# FINAL_PROJECT.net
KiCad netlist of a schematic drawn in EAGLE
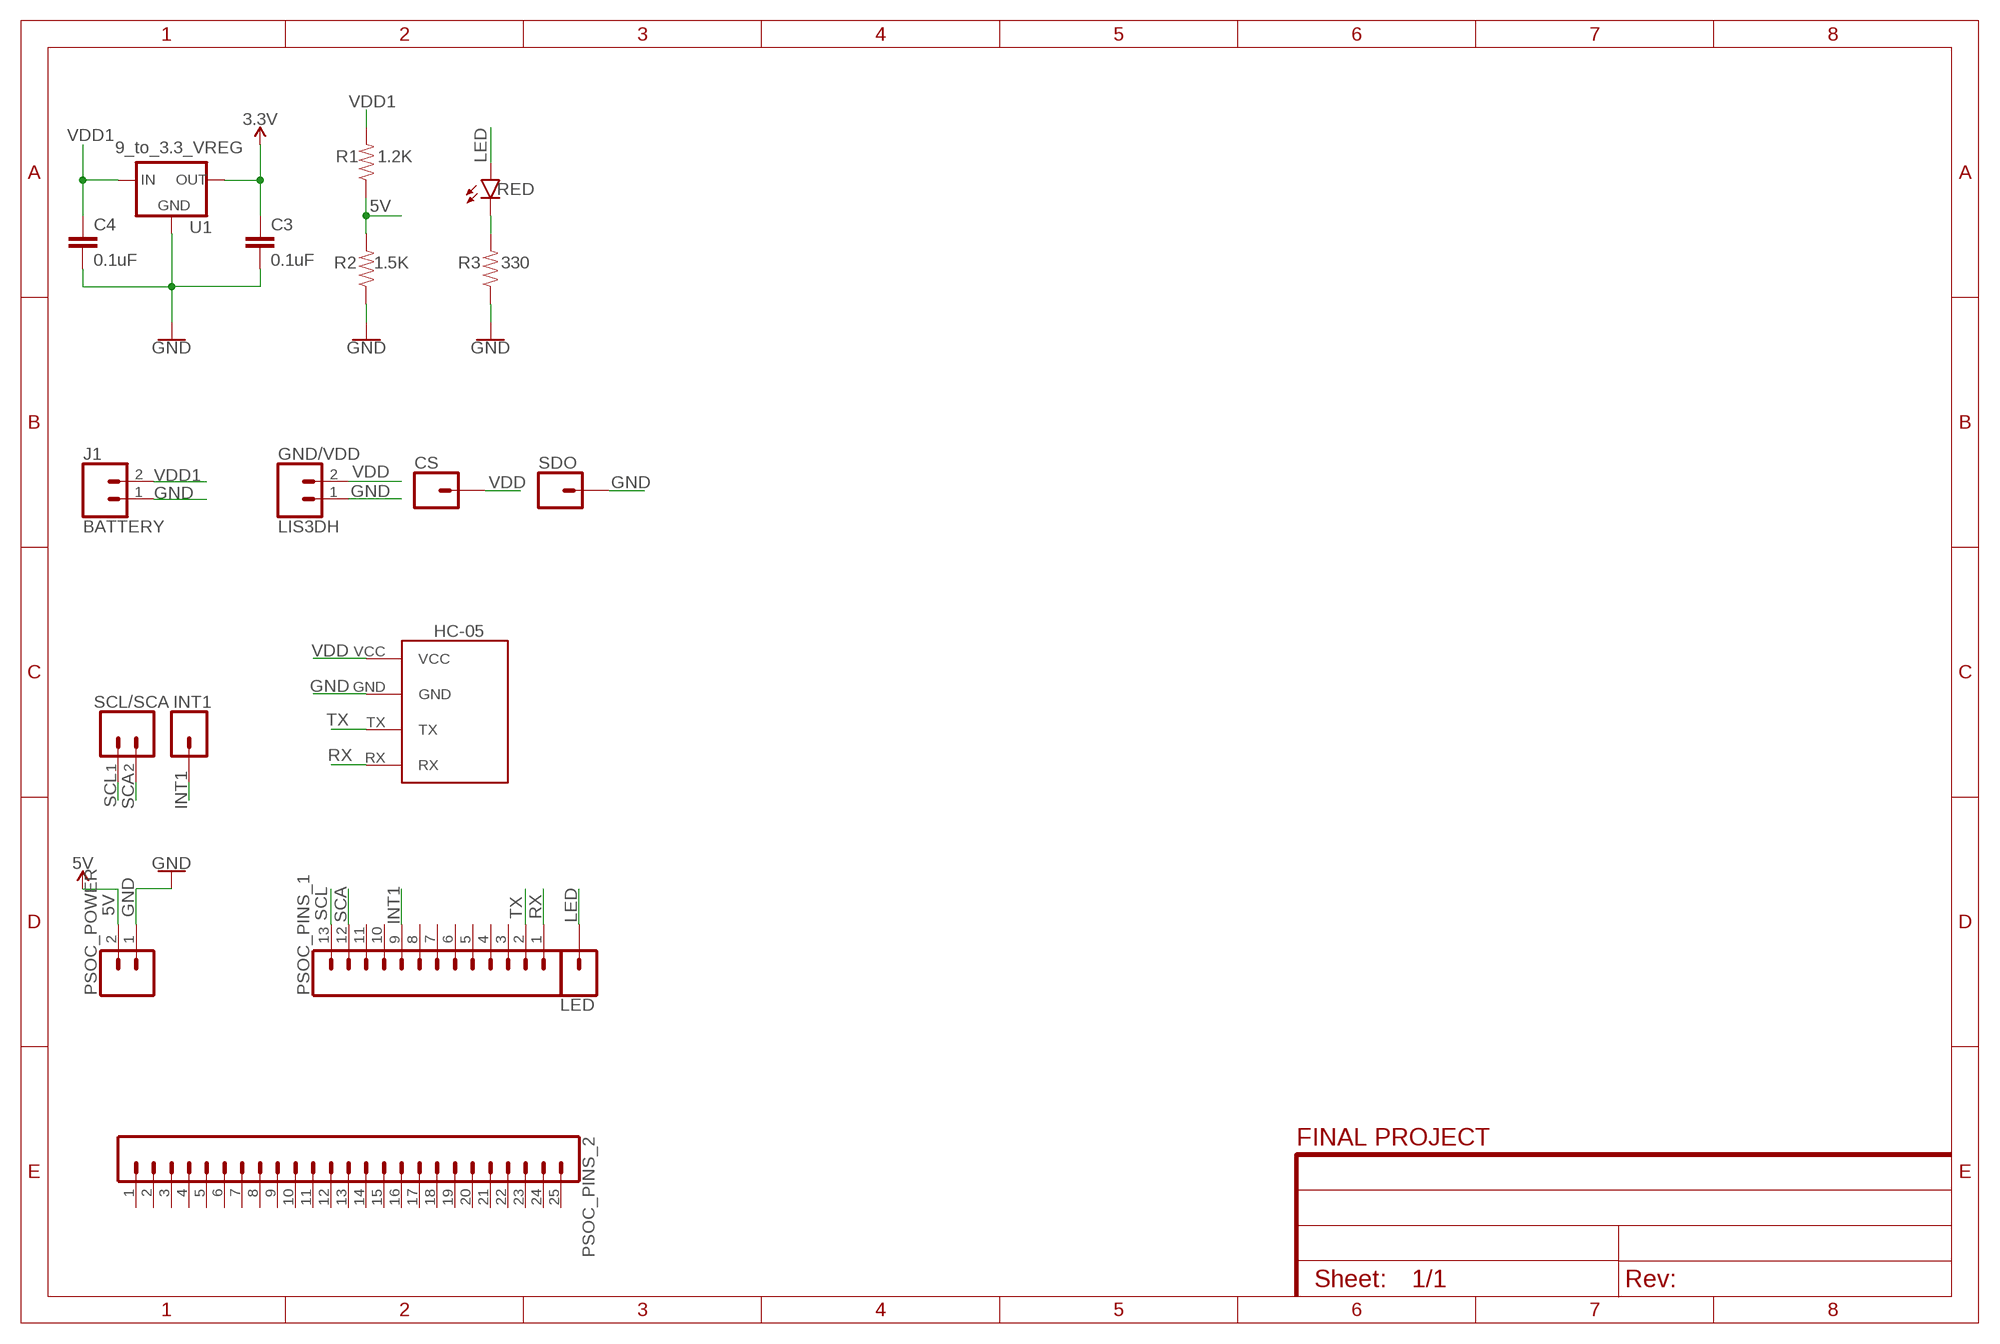
[diagram p0: schematic, sheet 1]

(export (version "E")
  (design (tool "Eeschema 10.0.6"))
  (components
    (comp (ref "C3")
      (value "0.1uF")
      (footprint "eagle-import:CAP-PTH-SMALL-KIT")
      (libsource (lib "eagle-import") (part "0.1UF-KIT-EZ-50V-20%"))
    )
    (comp (ref "C4")
      (value "0.1uF")
      (footprint "eagle-import:CAP-PTH-SMALL-KIT")
      (libsource (lib "eagle-import") (part "0.1UF-KIT-EZ-50V-20%"))
    )
    (comp (ref "CS")
      (value "CONN_01")
      (footprint "eagle-import:1X01")
      (libsource (lib "eagle-import") (part "CONN_01"))
    )
    (comp (ref "GND/VDD")
      (value "LIS3DH")
      (footprint "eagle-import:1X02")
      (libsource (lib "eagle-import") (part "CONN_02"))
    )
    (comp (ref "HC-05")
      (value "BLUETOOTH_BOARD")
      (footprint "eagle-import:BT_BOARD_FOOTPRINT")
      (libsource (lib "eagle-import") (part "BLUETOOTH_BOARD"))
    )
    (comp (ref "INT1")
      (value "CONN_01")
      (footprint "eagle-import:1X01")
      (libsource (lib "eagle-import") (part "CONN_01"))
    )
    (comp (ref "J1")
      (value "BATTERY")
      (footprint "eagle-import:1X02")
      (libsource (lib "eagle-import") (part "CONN_02"))
    )
    (comp (ref "LED")
      (value "CONN_01")
      (footprint "eagle-import:1X01")
      (libsource (lib "eagle-import") (part "CONN_01"))
    )
    (comp (ref "PSOC_PINS_1")
      (value "CONN_13")
      (footprint "eagle-import:1X13")
      (libsource (lib "eagle-import") (part "CONN_13"))
    )
    (comp (ref "PSOC_PINS_2")
      (value "CONN_25")
      (footprint "eagle-import:1X25")
      (libsource (lib "eagle-import") (part "CONN_25"))
    )
    (comp (ref "PSOC_POWER")
      (value "CONN_02")
      (footprint "eagle-import:1X02")
      (libsource (lib "eagle-import") (part "CONN_02"))
    )
    (comp (ref "R1")
      (value "1.2K")
      (footprint "eagle-import:AXIAL-0.3")
      (libsource (lib "eagle-import") (part "330OHM-HORIZ-1/10W-5%"))
    )
    (comp (ref "R2")
      (value "1.5K")
      (footprint "eagle-import:AXIAL-0.3")
      (libsource (lib "eagle-import") (part "330OHM-HORIZ-1/10W-5%"))
    )
    (comp (ref "R3")
      (value "330")
      (footprint "eagle-import:AXIAL-0.3")
      (libsource (lib "eagle-import") (part "330OHM-HORIZ-1/10W-5%"))
    )
    (comp (ref "RED")
      (value "LED3MM")
      (footprint "eagle-import:LED_3MM")
      (libsource (lib "eagle-import") (part "LED3MM"))
    )
    (comp (ref "SCL/SCA")
      (value "CONN_02")
      (footprint "eagle-import:1X02")
      (libsource (lib "eagle-import") (part "CONN_02"))
    )
    (comp (ref "SDO")
      (value "CONN_01")
      (footprint "eagle-import:1X01")
      (libsource (lib "eagle-import") (part "CONN_01"))
    )
    (comp (ref "U1")
      (value "9_to_3.3_VREG")
      (footprint "eagle-import:TO-92")
      (libsource (lib "eagle-import") (part "V_REG_78XXTO-92_UNTESTED"))
    )
  )
  (nets
    (net (code "1") (name "/INT1") (class "Default")
      (node (ref "INT1") (pin "1") (pinfunction "1_1") (pintype "passive"))
      (node (ref "PSOC_PINS_1") (pin "9") (pinfunction "9_9") (pintype "passive"))
    )
    (net (code "2") (name "/LED") (class "Default")
      (node (ref "LED") (pin "1") (pinfunction "1_1") (pintype "passive"))
      (node (ref "RED") (pin "A") (pinfunction "A_A") (pintype "passive"))
    )
    (net (code "3") (name "/RX") (class "Default")
      (node (ref "HC-05") (pin "RX") (pinfunction "RX_RX") (pintype "bidirectional"))
      (node (ref "PSOC_PINS_1") (pin "1") (pinfunction "1_1") (pintype "passive"))
    )
    (net (code "4") (name "/SCA") (class "Default")
      (node (ref "PSOC_PINS_1") (pin "12") (pinfunction "12_12") (pintype "passive"))
      (node (ref "SCL/SCA") (pin "2") (pinfunction "2_2") (pintype "passive"))
    )
    (net (code "5") (name "/SCL") (class "Default")
      (node (ref "PSOC_PINS_1") (pin "13") (pinfunction "13_13") (pintype "passive"))
      (node (ref "SCL/SCA") (pin "1") (pinfunction "1_1") (pintype "passive"))
    )
    (net (code "6") (name "/TX") (class "Default")
      (node (ref "HC-05") (pin "TX") (pinfunction "TX_TX") (pintype "bidirectional"))
      (node (ref "PSOC_PINS_1") (pin "2") (pinfunction "2_2") (pintype "passive"))
    )
    (net (code "7") (name "/VDD1") (class "Default")
      (node (ref "C4") (pin "1") (pinfunction "1_1") (pintype "passive"))
      (node (ref "J1") (pin "2") (pinfunction "2_2") (pintype "passive"))
      (node (ref "R1") (pin "P$2") (pinfunction "2_P$2") (pintype "passive"))
      (node (ref "U1") (pin "3") (pinfunction "IN_3") (pintype "input"))
    )
    (net (code "8") (name "3.3V") (class "Default")
      (node (ref "C3") (pin "1") (pinfunction "1_1") (pintype "passive"))
      (node (ref "CS") (pin "1") (pinfunction "1_1") (pintype "passive"))
      (node (ref "GND/VDD") (pin "2") (pinfunction "2_2") (pintype "passive"))
      (node (ref "HC-05") (pin "VCC") (pinfunction "VCC_VCC") (pintype "bidirectional"))
      (node (ref "U1") (pin "1") (pinfunction "OUT_1") (pintype "passive"))
    )
    (net (code "9") (name "5V") (class "Default")
      (node (ref "PSOC_POWER") (pin "2") (pinfunction "2_2") (pintype "passive"))
      (node (ref "R1") (pin "P$1") (pinfunction "1_P$1") (pintype "passive"))
      (node (ref "R2") (pin "P$2") (pinfunction "2_P$2") (pintype "passive"))
    )
    (net (code "10") (name "GND") (class "Default")
      (node (ref "C3") (pin "2") (pinfunction "2_2") (pintype "passive"))
      (node (ref "C4") (pin "2") (pinfunction "2_2") (pintype "passive"))
      (node (ref "GND/VDD") (pin "1") (pinfunction "1_1") (pintype "passive"))
      (node (ref "HC-05") (pin "GND") (pinfunction "GND_GND") (pintype "bidirectional"))
      (node (ref "J1") (pin "1") (pinfunction "1_1") (pintype "passive"))
      (node (ref "PSOC_POWER") (pin "1") (pinfunction "1_1") (pintype "passive"))
      (node (ref "R2") (pin "P$1") (pinfunction "1_P$1") (pintype "passive"))
      (node (ref "R3") (pin "P$1") (pinfunction "1_P$1") (pintype "passive"))
      (node (ref "SDO") (pin "1") (pinfunction "1_1") (pintype "passive"))
      (node (ref "U1") (pin "2") (pinfunction "GND_2") (pintype "input"))
    )
    (net (code "11") (name "Net-(R3-2)") (class "Default")
      (node (ref "R3") (pin "P$2") (pinfunction "2_P$2") (pintype "passive"))
      (node (ref "RED") (pin "K") (pinfunction "C_K") (pintype "passive"))
    )
    (net (code "12") (name "unconnected-(PSOC_PINS_1-Pad3)") (class "Default")
      (node (ref "PSOC_PINS_1") (pin "3") (pinfunction "3_3") (pintype "passive"))
    )
    (net (code "13") (name "unconnected-(PSOC_PINS_1-Pad4)") (class "Default")
      (node (ref "PSOC_PINS_1") (pin "4") (pinfunction "4_4") (pintype "passive"))
    )
    (net (code "14") (name "unconnected-(PSOC_PINS_1-Pad5)") (class "Default")
      (node (ref "PSOC_PINS_1") (pin "5") (pinfunction "5_5") (pintype "passive"))
    )
    (net (code "15") (name "unconnected-(PSOC_PINS_1-Pad6)") (class "Default")
      (node (ref "PSOC_PINS_1") (pin "6") (pinfunction "6_6") (pintype "passive"))
    )
    (net (code "16") (name "unconnected-(PSOC_PINS_1-Pad7)") (class "Default")
      (node (ref "PSOC_PINS_1") (pin "7") (pinfunction "7_7") (pintype "passive"))
    )
    (net (code "17") (name "unconnected-(PSOC_PINS_1-Pad8)") (class "Default")
      (node (ref "PSOC_PINS_1") (pin "8") (pinfunction "8_8") (pintype "passive"))
    )
    (net (code "18") (name "unconnected-(PSOC_PINS_1-Pad10)") (class "Default")
      (node (ref "PSOC_PINS_1") (pin "10") (pinfunction "10_10") (pintype "passive"))
    )
    (net (code "19") (name "unconnected-(PSOC_PINS_1-Pad11)") (class "Default")
      (node (ref "PSOC_PINS_1") (pin "11") (pinfunction "11_11") (pintype "passive"))
    )
    (net (code "20") (name "unconnected-(PSOC_PINS_2-Pad1)") (class "Default")
      (node (ref "PSOC_PINS_2") (pin "1") (pinfunction "1_1") (pintype "passive"))
    )
    (net (code "21") (name "unconnected-(PSOC_PINS_2-Pad2)") (class "Default")
      (node (ref "PSOC_PINS_2") (pin "2") (pinfunction "2_2") (pintype "passive"))
    )
    (net (code "22") (name "unconnected-(PSOC_PINS_2-Pad3)") (class "Default")
      (node (ref "PSOC_PINS_2") (pin "3") (pinfunction "3_3") (pintype "passive"))
    )
    (net (code "23") (name "unconnected-(PSOC_PINS_2-Pad4)") (class "Default")
      (node (ref "PSOC_PINS_2") (pin "4") (pinfunction "4_4") (pintype "passive"))
    )
    (net (code "24") (name "unconnected-(PSOC_PINS_2-Pad5)") (class "Default")
      (node (ref "PSOC_PINS_2") (pin "5") (pinfunction "5_5") (pintype "passive"))
    )
    (net (code "25") (name "unconnected-(PSOC_PINS_2-Pad6)") (class "Default")
      (node (ref "PSOC_PINS_2") (pin "6") (pinfunction "6_6") (pintype "passive"))
    )
    (net (code "26") (name "unconnected-(PSOC_PINS_2-Pad7)") (class "Default")
      (node (ref "PSOC_PINS_2") (pin "7") (pinfunction "7_7") (pintype "passive"))
    )
    (net (code "27") (name "unconnected-(PSOC_PINS_2-Pad8)") (class "Default")
      (node (ref "PSOC_PINS_2") (pin "8") (pinfunction "8_8") (pintype "passive"))
    )
    (net (code "28") (name "unconnected-(PSOC_PINS_2-Pad9)") (class "Default")
      (node (ref "PSOC_PINS_2") (pin "9") (pinfunction "9_9") (pintype "passive"))
    )
    (net (code "29") (name "unconnected-(PSOC_PINS_2-Pad10)") (class "Default")
      (node (ref "PSOC_PINS_2") (pin "10") (pinfunction "10_10") (pintype "passive"))
    )
    (net (code "30") (name "unconnected-(PSOC_PINS_2-Pad11)") (class "Default")
      (node (ref "PSOC_PINS_2") (pin "11") (pinfunction "11_11") (pintype "passive"))
    )
    (net (code "31") (name "unconnected-(PSOC_PINS_2-Pad12)") (class "Default")
      (node (ref "PSOC_PINS_2") (pin "12") (pinfunction "12_12") (pintype "passive"))
    )
    (net (code "32") (name "unconnected-(PSOC_PINS_2-Pad13)") (class "Default")
      (node (ref "PSOC_PINS_2") (pin "13") (pinfunction "13_13") (pintype "passive"))
    )
    (net (code "33") (name "unconnected-(PSOC_PINS_2-Pad14)") (class "Default")
      (node (ref "PSOC_PINS_2") (pin "14") (pinfunction "14_14") (pintype "passive"))
    )
    (net (code "34") (name "unconnected-(PSOC_PINS_2-Pad15)") (class "Default")
      (node (ref "PSOC_PINS_2") (pin "15") (pinfunction "15_15") (pintype "passive"))
    )
    (net (code "35") (name "unconnected-(PSOC_PINS_2-Pad16)") (class "Default")
      (node (ref "PSOC_PINS_2") (pin "16") (pinfunction "16_16") (pintype "passive"))
    )
    (net (code "36") (name "unconnected-(PSOC_PINS_2-Pad17)") (class "Default")
      (node (ref "PSOC_PINS_2") (pin "17") (pinfunction "17_17") (pintype "passive"))
    )
    (net (code "37") (name "unconnected-(PSOC_PINS_2-Pad18)") (class "Default")
      (node (ref "PSOC_PINS_2") (pin "18") (pinfunction "18_18") (pintype "passive"))
    )
    (net (code "38") (name "unconnected-(PSOC_PINS_2-Pad19)") (class "Default")
      (node (ref "PSOC_PINS_2") (pin "19") (pinfunction "19_19") (pintype "passive"))
    )
    (net (code "39") (name "unconnected-(PSOC_PINS_2-Pad20)") (class "Default")
      (node (ref "PSOC_PINS_2") (pin "20") (pinfunction "20_20") (pintype "passive"))
    )
    (net (code "40") (name "unconnected-(PSOC_PINS_2-Pad21)") (class "Default")
      (node (ref "PSOC_PINS_2") (pin "21") (pinfunction "21_21") (pintype "passive"))
    )
    (net (code "41") (name "unconnected-(PSOC_PINS_2-Pad22)") (class "Default")
      (node (ref "PSOC_PINS_2") (pin "22") (pinfunction "22_22") (pintype "passive"))
    )
    (net (code "42") (name "unconnected-(PSOC_PINS_2-Pad23)") (class "Default")
      (node (ref "PSOC_PINS_2") (pin "23") (pinfunction "23_23") (pintype "passive"))
    )
    (net (code "43") (name "unconnected-(PSOC_PINS_2-Pad24)") (class "Default")
      (node (ref "PSOC_PINS_2") (pin "24") (pinfunction "24_24") (pintype "passive"))
    )
    (net (code "44") (name "unconnected-(PSOC_PINS_2-Pad25)") (class "Default")
      (node (ref "PSOC_PINS_2") (pin "25") (pinfunction "25_25") (pintype "passive"))
    )
  )
)
